# quad_decay_v1_0_2.net
KiCad netlist of a schematic drawn in EAGLE
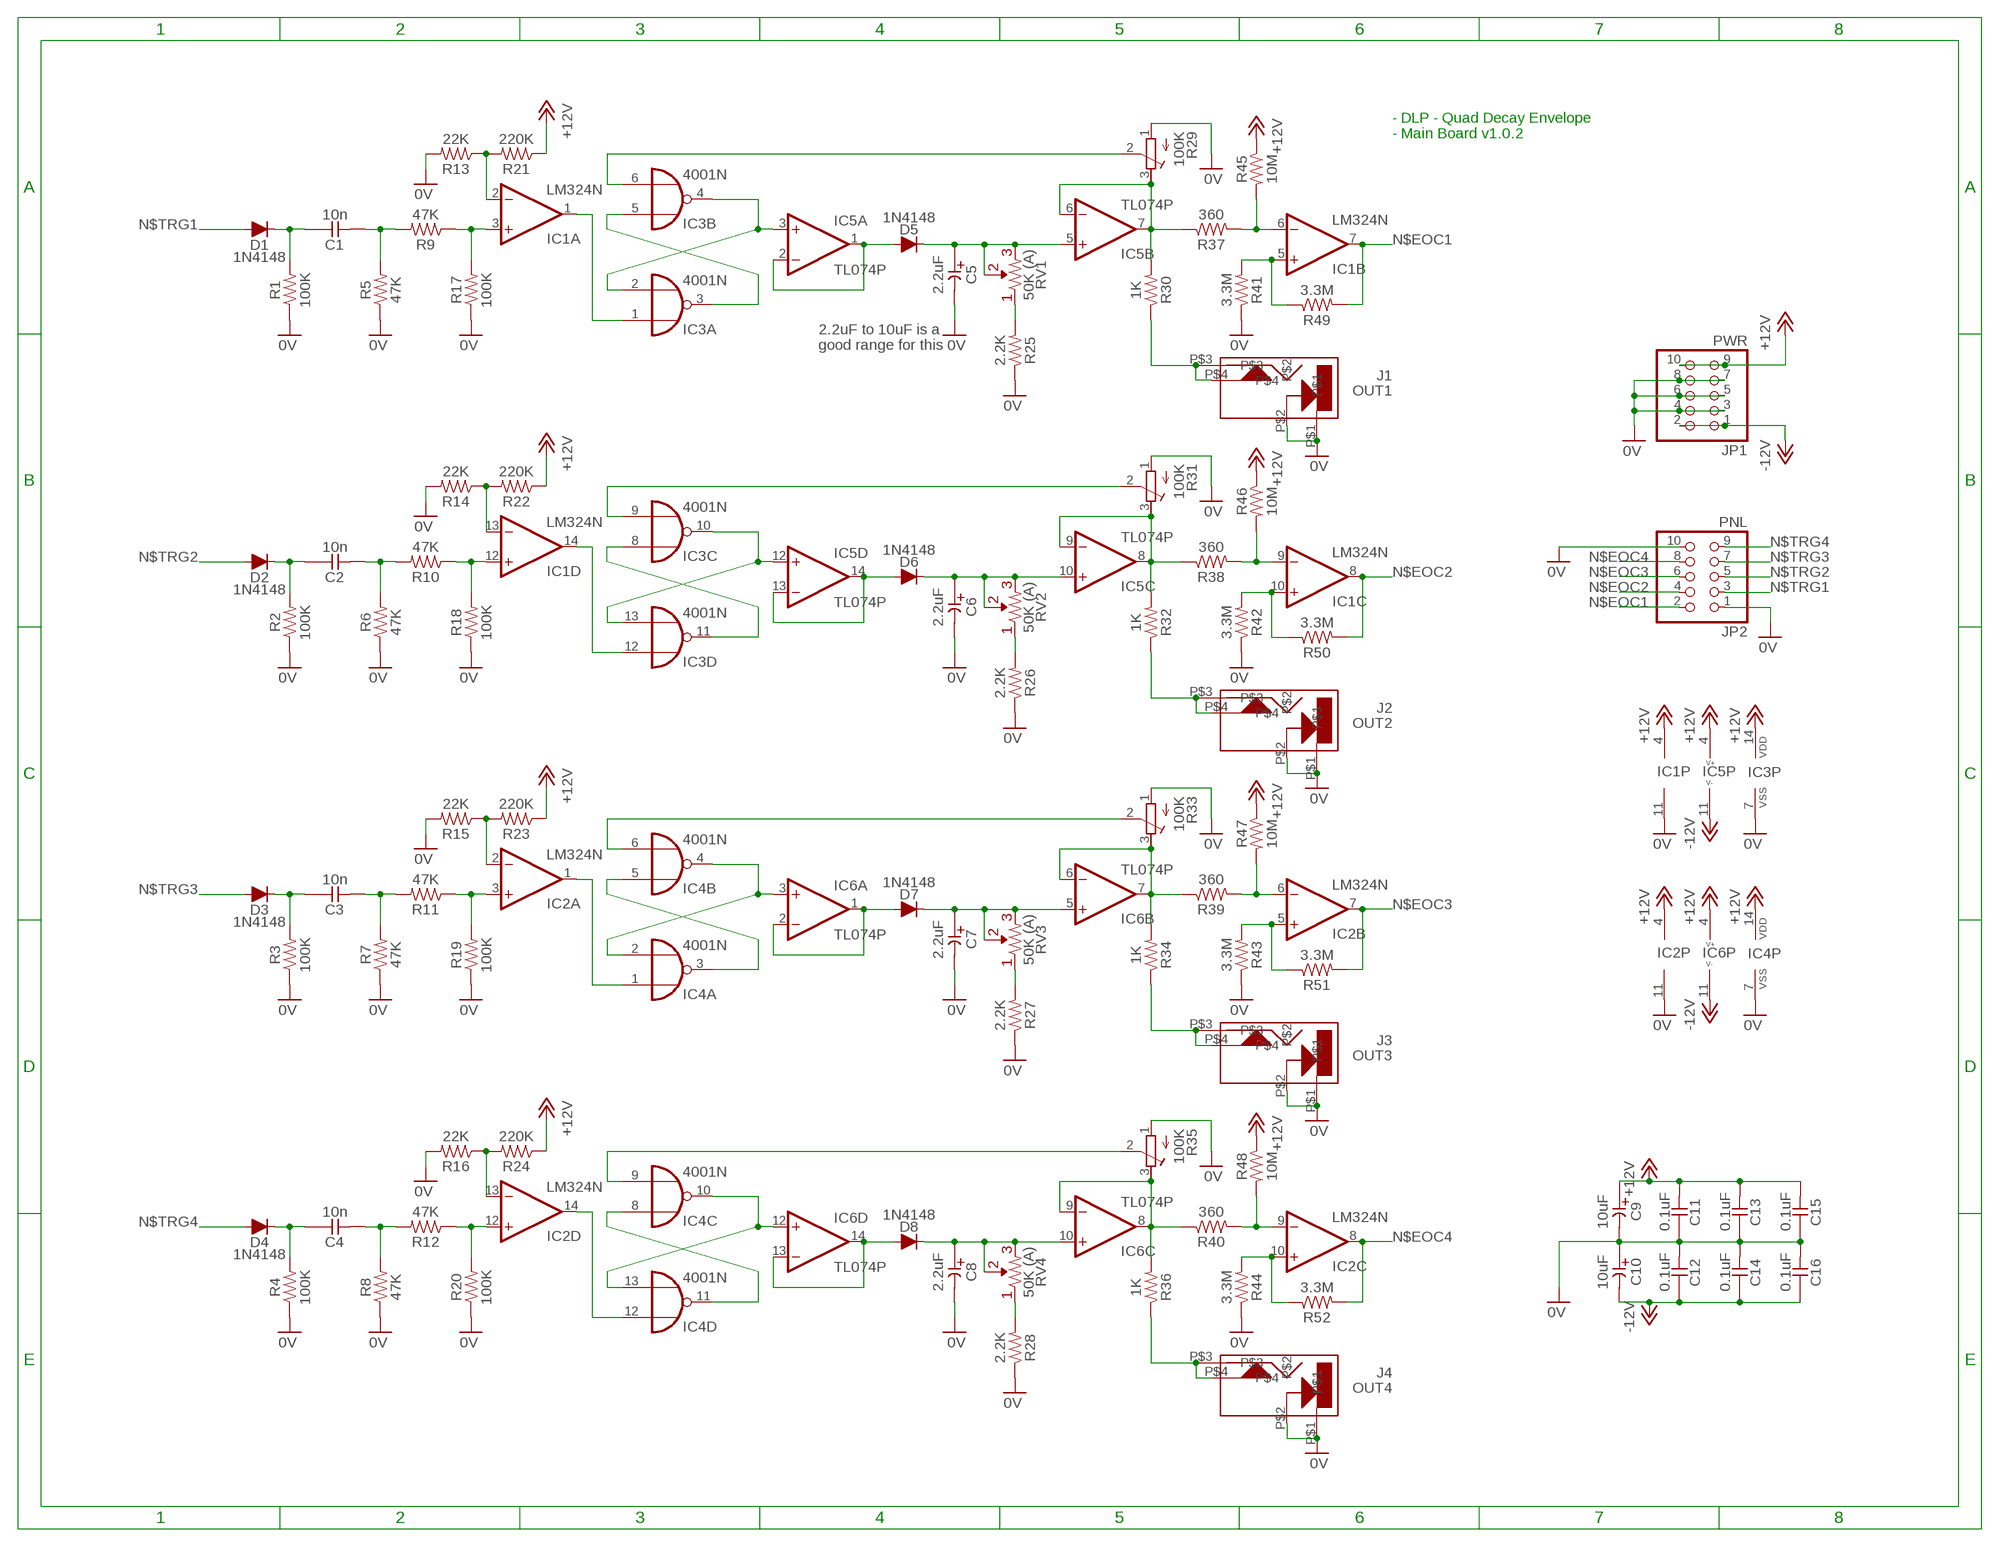
[diagram p0: schematic, sheet 1]

(export (version "E")
  (design (tool "Eeschema 10.0.6"))
  (components
    (comp (ref "C1")
      (value "10n")
      (footprint "eagle-import:C025-024X044")
      (libsource (lib "eagle-import") (part "CC-US025-024X044"))
    )
    (comp (ref "C2")
      (value "10n")
      (footprint "eagle-import:C025-024X044")
      (libsource (lib "eagle-import") (part "CC-US025-024X044"))
    )
    (comp (ref "C3")
      (value "10n")
      (footprint "eagle-import:C025-024X044")
      (libsource (lib "eagle-import") (part "CC-US025-024X044"))
    )
    (comp (ref "C4")
      (value "10n")
      (footprint "eagle-import:C025-024X044")
      (libsource (lib "eagle-import") (part "CC-US025-024X044"))
    )
    (comp (ref "C5")
      (value "2.2uF")
      (footprint "eagle-import:E2-5")
      (libsource (lib "eagle-import") (part "CE-USE2-5"))
    )
    (comp (ref "C6")
      (value "2.2uF")
      (footprint "eagle-import:E2-5")
      (libsource (lib "eagle-import") (part "CE-USE2-5"))
    )
    (comp (ref "C7")
      (value "2.2uF")
      (footprint "eagle-import:E2-5")
      (libsource (lib "eagle-import") (part "CE-USE2-5"))
    )
    (comp (ref "C8")
      (value "2.2uF")
      (footprint "eagle-import:E2-5")
      (libsource (lib "eagle-import") (part "CE-USE2-5"))
    )
    (comp (ref "C9")
      (value "10uF")
      (footprint "eagle-import:E2-5")
      (libsource (lib "eagle-import") (part "CE-USE2-5"))
    )
    (comp (ref "C10")
      (value "10uF")
      (footprint "eagle-import:E2-5")
      (libsource (lib "eagle-import") (part "CE-USE2-5"))
    )
    (comp (ref "C11")
      (value "0.1uF")
      (footprint "eagle-import:C025-024X044")
      (libsource (lib "eagle-import") (part "CC-US025-024X044"))
    )
    (comp (ref "C12")
      (value "0.1uF")
      (footprint "eagle-import:C025-024X044")
      (libsource (lib "eagle-import") (part "CC-US025-024X044"))
    )
    (comp (ref "C13")
      (value "0.1uF")
      (footprint "eagle-import:C025-024X044")
      (libsource (lib "eagle-import") (part "CC-US025-024X044"))
    )
    (comp (ref "C14")
      (value "0.1uF")
      (footprint "eagle-import:C025-024X044")
      (libsource (lib "eagle-import") (part "CC-US025-024X044"))
    )
    (comp (ref "C15")
      (value "0.1uF")
      (footprint "eagle-import:C025-024X044")
      (libsource (lib "eagle-import") (part "CC-US025-024X044"))
    )
    (comp (ref "C16")
      (value "0.1uF")
      (footprint "eagle-import:C025-024X044")
      (libsource (lib "eagle-import") (part "CC-US025-024X044"))
    )
    (comp (ref "D1")
      (value "1N4148")
      (footprint "eagle-import:DO34-5")
      (libsource (lib "eagle-import") (part "1N4148"))
    )
    (comp (ref "D2")
      (value "1N4148")
      (footprint "eagle-import:DO34-5")
      (libsource (lib "eagle-import") (part "1N4148"))
    )
    (comp (ref "D3")
      (value "1N4148")
      (footprint "eagle-import:DO34-5")
      (libsource (lib "eagle-import") (part "1N4148"))
    )
    (comp (ref "D4")
      (value "1N4148")
      (footprint "eagle-import:DO34-5")
      (libsource (lib "eagle-import") (part "1N4148"))
    )
    (comp (ref "D5")
      (value "1N4148")
      (footprint "eagle-import:DO34-5")
      (libsource (lib "eagle-import") (part "1N4148"))
    )
    (comp (ref "D6")
      (value "1N4148")
      (footprint "eagle-import:DO34-5")
      (libsource (lib "eagle-import") (part "1N4148"))
    )
    (comp (ref "D7")
      (value "1N4148")
      (footprint "eagle-import:DO34-5")
      (libsource (lib "eagle-import") (part "1N4148"))
    )
    (comp (ref "D8")
      (value "1N4148")
      (footprint "eagle-import:DO34-5")
      (libsource (lib "eagle-import") (part "1N4148"))
    )
    (comp (ref "IC1")
      (value "LM324N")
      (footprint "eagle-import:DIL14")
      (libsource (lib "eagle-import") (part "LM324N"))
    )
    (comp (ref "IC2")
      (value "LM324N")
      (footprint "eagle-import:DIL14")
      (libsource (lib "eagle-import") (part "LM324N"))
    )
    (comp (ref "IC3")
      (value "4001N")
      (footprint "eagle-import:DIL14")
      (libsource (lib "eagle-import") (part "4001N"))
    )
    (comp (ref "IC4")
      (value "4001N")
      (footprint "eagle-import:DIL14")
      (libsource (lib "eagle-import") (part "4001N"))
    )
    (comp (ref "IC5")
      (value "TL074P")
      (footprint "eagle-import:DIL14")
      (libsource (lib "eagle-import") (part "TL074P"))
    )
    (comp (ref "IC6")
      (value "TL074P")
      (footprint "eagle-import:DIL14")
      (libsource (lib "eagle-import") (part "TL074P"))
    )
    (comp (ref "J1")
      (value "OUT1")
      (footprint "eagle-import:CL1384")
      (libsource (lib "eagle-import") (part "CL1384"))
    )
    (comp (ref "J2")
      (value "OUT2")
      (footprint "eagle-import:CL1384")
      (libsource (lib "eagle-import") (part "CL1384"))
    )
    (comp (ref "J3")
      (value "OUT3")
      (footprint "eagle-import:CL1384")
      (libsource (lib "eagle-import") (part "CL1384"))
    )
    (comp (ref "J4")
      (value "OUT4")
      (footprint "eagle-import:CL1384")
      (libsource (lib "eagle-import") (part "CL1384"))
    )
    (comp (ref "JP1")
      (value "PWR")
      (footprint "eagle-import:2X05")
      (libsource (lib "eagle-import") (part "PINHD-2X5"))
    )
    (comp (ref "JP2")
      (value "PNL")
      (footprint "eagle-import:2X05")
      (libsource (lib "eagle-import") (part "PINHD-2X5"))
    )
    (comp (ref "R1")
      (value "100K")
      (footprint "eagle-import:0207_7")
      (libsource (lib "eagle-import") (part "R"))
    )
    (comp (ref "R2")
      (value "100K")
      (footprint "eagle-import:0207_7")
      (libsource (lib "eagle-import") (part "R"))
    )
    (comp (ref "R3")
      (value "100K")
      (footprint "eagle-import:0207_7")
      (libsource (lib "eagle-import") (part "R"))
    )
    (comp (ref "R4")
      (value "100K")
      (footprint "eagle-import:0207_7")
      (libsource (lib "eagle-import") (part "R"))
    )
    (comp (ref "R5")
      (value "47K")
      (footprint "eagle-import:0207_7")
      (libsource (lib "eagle-import") (part "R"))
    )
    (comp (ref "R6")
      (value "47K")
      (footprint "eagle-import:0207_7")
      (libsource (lib "eagle-import") (part "R"))
    )
    (comp (ref "R7")
      (value "47K")
      (footprint "eagle-import:0207_7")
      (libsource (lib "eagle-import") (part "R"))
    )
    (comp (ref "R8")
      (value "47K")
      (footprint "eagle-import:0207_7")
      (libsource (lib "eagle-import") (part "R"))
    )
    (comp (ref "R9")
      (value "47K")
      (footprint "eagle-import:0207_7")
      (libsource (lib "eagle-import") (part "R"))
    )
    (comp (ref "R10")
      (value "47K")
      (footprint "eagle-import:0207_7")
      (libsource (lib "eagle-import") (part "R"))
    )
    (comp (ref "R11")
      (value "47K")
      (footprint "eagle-import:0207_7")
      (libsource (lib "eagle-import") (part "R"))
    )
    (comp (ref "R12")
      (value "47K")
      (footprint "eagle-import:0207_7")
      (libsource (lib "eagle-import") (part "R"))
    )
    (comp (ref "R13")
      (value "22K")
      (footprint "eagle-import:0207_7")
      (libsource (lib "eagle-import") (part "R"))
    )
    (comp (ref "R14")
      (value "22K")
      (footprint "eagle-import:0207_7")
      (libsource (lib "eagle-import") (part "R"))
    )
    (comp (ref "R15")
      (value "22K")
      (footprint "eagle-import:0207_7")
      (libsource (lib "eagle-import") (part "R"))
    )
    (comp (ref "R16")
      (value "22K")
      (footprint "eagle-import:0207_7")
      (libsource (lib "eagle-import") (part "R"))
    )
    (comp (ref "R17")
      (value "100K")
      (footprint "eagle-import:0207_7")
      (libsource (lib "eagle-import") (part "R"))
    )
    (comp (ref "R18")
      (value "100K")
      (footprint "eagle-import:0207_7")
      (libsource (lib "eagle-import") (part "R"))
    )
    (comp (ref "R19")
      (value "100K")
      (footprint "eagle-import:0207_7")
      (libsource (lib "eagle-import") (part "R"))
    )
    (comp (ref "R20")
      (value "100K")
      (footprint "eagle-import:0207_7")
      (libsource (lib "eagle-import") (part "R"))
    )
    (comp (ref "R21")
      (value "220K")
      (footprint "eagle-import:0207_7")
      (libsource (lib "eagle-import") (part "R"))
    )
    (comp (ref "R22")
      (value "220K")
      (footprint "eagle-import:0207_7")
      (libsource (lib "eagle-import") (part "R"))
    )
    (comp (ref "R23")
      (value "220K")
      (footprint "eagle-import:0207_7")
      (libsource (lib "eagle-import") (part "R"))
    )
    (comp (ref "R24")
      (value "220K")
      (footprint "eagle-import:0207_7")
      (libsource (lib "eagle-import") (part "R"))
    )
    (comp (ref "R25")
      (value "2.2K")
      (footprint "eagle-import:0207_7")
      (libsource (lib "eagle-import") (part "R"))
    )
    (comp (ref "R26")
      (value "2.2K")
      (footprint "eagle-import:0207_7")
      (libsource (lib "eagle-import") (part "R"))
    )
    (comp (ref "R27")
      (value "2.2K")
      (footprint "eagle-import:0207_7")
      (libsource (lib "eagle-import") (part "R"))
    )
    (comp (ref "R28")
      (value "2.2K")
      (footprint "eagle-import:0207_7")
      (libsource (lib "eagle-import") (part "R"))
    )
    (comp (ref "R29")
      (value "100K")
      (footprint "eagle-import:RTRIM3339P")
      (libsource (lib "eagle-import") (part "R-TRIMM3339P"))
    )
    (comp (ref "R30")
      (value "1K")
      (footprint "eagle-import:0207_7")
      (libsource (lib "eagle-import") (part "R"))
    )
    (comp (ref "R31")
      (value "100K")
      (footprint "eagle-import:RTRIM3339P")
      (libsource (lib "eagle-import") (part "R-TRIMM3339P"))
    )
    (comp (ref "R32")
      (value "1K")
      (footprint "eagle-import:0207_7")
      (libsource (lib "eagle-import") (part "R"))
    )
    (comp (ref "R33")
      (value "100K")
      (footprint "eagle-import:RTRIM3339P")
      (libsource (lib "eagle-import") (part "R-TRIMM3339P"))
    )
    (comp (ref "R34")
      (value "1K")
      (footprint "eagle-import:0207_7")
      (libsource (lib "eagle-import") (part "R"))
    )
    (comp (ref "R35")
      (value "100K")
      (footprint "eagle-import:RTRIM3339P")
      (libsource (lib "eagle-import") (part "R-TRIMM3339P"))
    )
    (comp (ref "R36")
      (value "1K")
      (footprint "eagle-import:0207_7")
      (libsource (lib "eagle-import") (part "R"))
    )
    (comp (ref "R37")
      (value "360")
      (footprint "eagle-import:0207_7")
      (libsource (lib "eagle-import") (part "R"))
    )
    (comp (ref "R38")
      (value "360")
      (footprint "eagle-import:0207_7")
      (libsource (lib "eagle-import") (part "R"))
    )
    (comp (ref "R39")
      (value "360")
      (footprint "eagle-import:0207_7")
      (libsource (lib "eagle-import") (part "R"))
    )
    (comp (ref "R40")
      (value "360")
      (footprint "eagle-import:0207_7")
      (libsource (lib "eagle-import") (part "R"))
    )
    (comp (ref "R41")
      (value "3.3M")
      (footprint "eagle-import:0207_7")
      (libsource (lib "eagle-import") (part "R"))
    )
    (comp (ref "R42")
      (value "3.3M")
      (footprint "eagle-import:0207_7")
      (libsource (lib "eagle-import") (part "R"))
    )
    (comp (ref "R43")
      (value "3.3M")
      (footprint "eagle-import:0207_7")
      (libsource (lib "eagle-import") (part "R"))
    )
    (comp (ref "R44")
      (value "3.3M")
      (footprint "eagle-import:0207_7")
      (libsource (lib "eagle-import") (part "R"))
    )
    (comp (ref "R45")
      (value "10M")
      (footprint "eagle-import:0207_7")
      (libsource (lib "eagle-import") (part "R"))
    )
    (comp (ref "R46")
      (value "10M")
      (footprint "eagle-import:0207_7")
      (libsource (lib "eagle-import") (part "R"))
    )
    (comp (ref "R47")
      (value "10M")
      (footprint "eagle-import:0207_7")
      (libsource (lib "eagle-import") (part "R"))
    )
    (comp (ref "R48")
      (value "10M")
      (footprint "eagle-import:0207_7")
      (libsource (lib "eagle-import") (part "R"))
    )
    (comp (ref "R49")
      (value "3.3M")
      (footprint "eagle-import:0207_7")
      (libsource (lib "eagle-import") (part "R"))
    )
    (comp (ref "R50")
      (value "3.3M")
      (footprint "eagle-import:0207_7")
      (libsource (lib "eagle-import") (part "R"))
    )
    (comp (ref "R51")
      (value "3.3M")
      (footprint "eagle-import:0207_7")
      (libsource (lib "eagle-import") (part "R"))
    )
    (comp (ref "R52")
      (value "3.3M")
      (footprint "eagle-import:0207_7")
      (libsource (lib "eagle-import") (part "R"))
    )
    (comp (ref "RV1")
      (value "50K (A)")
      (footprint "eagle-import:R-VAR")
      (libsource (lib "eagle-import") (part "R-VAR"))
    )
    (comp (ref "RV2")
      (value "50K (A)")
      (footprint "eagle-import:R-VAR")
      (libsource (lib "eagle-import") (part "R-VAR"))
    )
    (comp (ref "RV3")
      (value "50K (A)")
      (footprint "eagle-import:R-VAR")
      (libsource (lib "eagle-import") (part "R-VAR"))
    )
    (comp (ref "RV4")
      (value "50K (A)")
      (footprint "eagle-import:R-VAR")
      (libsource (lib "eagle-import") (part "R-VAR"))
    )
  )
  (nets
    (net (code "1") (name "+12V") (class "Default")
      (node (ref "C11") (pin "2") (pinfunction "2_2") (pintype "passive"))
      (node (ref "C13") (pin "2") (pinfunction "2_2") (pintype "passive"))
      (node (ref "C15") (pin "2") (pinfunction "2_2") (pintype "passive"))
      (node (ref "C9") (pin "+") (pinfunction "+_+") (pintype "passive"))
      (node (ref "IC1") (pin "4") (pinfunction "V+_4") (pintype "power_in"))
      (node (ref "IC2") (pin "4") (pinfunction "V+_4") (pintype "power_in"))
      (node (ref "IC3") (pin "14") (pinfunction "VDD_14") (pintype "power_in"))
      (node (ref "IC4") (pin "14") (pinfunction "VDD_14") (pintype "power_in"))
      (node (ref "IC5") (pin "4") (pinfunction "V+_4") (pintype "power_in"))
      (node (ref "IC6") (pin "4") (pinfunction "V+_4") (pintype "power_in"))
      (node (ref "JP1") (pin "10") (pinfunction "10_10") (pintype "passive"))
      (node (ref "JP1") (pin "9") (pinfunction "9_9") (pintype "passive"))
      (node (ref "R21") (pin "1") (pinfunction "1_1") (pintype "passive"))
      (node (ref "R22") (pin "1") (pinfunction "1_1") (pintype "passive"))
      (node (ref "R23") (pin "1") (pinfunction "1_1") (pintype "passive"))
      (node (ref "R24") (pin "1") (pinfunction "1_1") (pintype "passive"))
      (node (ref "R45") (pin "1") (pinfunction "1_1") (pintype "passive"))
      (node (ref "R46") (pin "1") (pinfunction "1_1") (pintype "passive"))
      (node (ref "R47") (pin "1") (pinfunction "1_1") (pintype "passive"))
      (node (ref "R48") (pin "1") (pinfunction "1_1") (pintype "passive"))
    )
    (net (code "2") (name "-12V") (class "Default")
      (node (ref "C10") (pin "-") (pinfunction "-_-") (pintype "passive"))
      (node (ref "C12") (pin "1") (pinfunction "1_1") (pintype "passive"))
      (node (ref "C14") (pin "1") (pinfunction "1_1") (pintype "passive"))
      (node (ref "C16") (pin "1") (pinfunction "1_1") (pintype "passive"))
      (node (ref "IC5") (pin "11") (pinfunction "V-_11") (pintype "power_in"))
      (node (ref "IC6") (pin "11") (pinfunction "V-_11") (pintype "power_in"))
      (node (ref "JP1") (pin "1") (pinfunction "1_1") (pintype "passive"))
      (node (ref "JP1") (pin "2") (pinfunction "2_2") (pintype "passive"))
    )
    (net (code "3") (name "/N$EOC1") (class "Default")
      (node (ref "IC1") (pin "7") (pinfunction "OUT_7") (pintype "output"))
      (node (ref "JP2") (pin "2") (pinfunction "2_2") (pintype "passive"))
      (node (ref "R49") (pin "2") (pinfunction "2_2") (pintype "passive"))
    )
    (net (code "4") (name "/N$EOC2") (class "Default")
      (node (ref "IC1") (pin "8") (pinfunction "OUT_8") (pintype "output"))
      (node (ref "JP2") (pin "4") (pinfunction "4_4") (pintype "passive"))
      (node (ref "R50") (pin "2") (pinfunction "2_2") (pintype "passive"))
    )
    (net (code "5") (name "/N$EOC3") (class "Default")
      (node (ref "IC2") (pin "7") (pinfunction "OUT_7") (pintype "output"))
      (node (ref "JP2") (pin "6") (pinfunction "6_6") (pintype "passive"))
      (node (ref "R51") (pin "2") (pinfunction "2_2") (pintype "passive"))
    )
    (net (code "6") (name "/N$EOC4") (class "Default")
      (node (ref "IC2") (pin "8") (pinfunction "OUT_8") (pintype "output"))
      (node (ref "JP2") (pin "8") (pinfunction "8_8") (pintype "passive"))
      (node (ref "R52") (pin "2") (pinfunction "2_2") (pintype "passive"))
    )
    (net (code "7") (name "/N$TRG1") (class "Default")
      (node (ref "D1") (pin "A") (pinfunction "A_A") (pintype "passive"))
      (node (ref "JP2") (pin "3") (pinfunction "3_3") (pintype "passive"))
    )
    (net (code "8") (name "/N$TRG2") (class "Default")
      (node (ref "D2") (pin "A") (pinfunction "A_A") (pintype "passive"))
      (node (ref "JP2") (pin "5") (pinfunction "5_5") (pintype "passive"))
    )
    (net (code "9") (name "/N$TRG3") (class "Default")
      (node (ref "D3") (pin "A") (pinfunction "A_A") (pintype "passive"))
      (node (ref "JP2") (pin "7") (pinfunction "7_7") (pintype "passive"))
    )
    (net (code "10") (name "/N$TRG4") (class "Default")
      (node (ref "D4") (pin "A") (pinfunction "A_A") (pintype "passive"))
      (node (ref "JP2") (pin "9") (pinfunction "9_9") (pintype "passive"))
    )
    (net (code "11") (name "0V") (class "Default")
      (node (ref "C10") (pin "+") (pinfunction "+_+") (pintype "passive"))
      (node (ref "C11") (pin "1") (pinfunction "1_1") (pintype "passive"))
      (node (ref "C12") (pin "2") (pinfunction "2_2") (pintype "passive"))
      (node (ref "C13") (pin "1") (pinfunction "1_1") (pintype "passive"))
      (node (ref "C14") (pin "2") (pinfunction "2_2") (pintype "passive"))
      (node (ref "C15") (pin "1") (pinfunction "1_1") (pintype "passive"))
      (node (ref "C16") (pin "2") (pinfunction "2_2") (pintype "passive"))
      (node (ref "C5") (pin "-") (pinfunction "-_-") (pintype "passive"))
      (node (ref "C6") (pin "-") (pinfunction "-_-") (pintype "passive"))
      (node (ref "C7") (pin "-") (pinfunction "-_-") (pintype "passive"))
      (node (ref "C8") (pin "-") (pinfunction "-_-") (pintype "passive"))
      (node (ref "C9") (pin "-") (pinfunction "-_-") (pintype "passive"))
      (node (ref "IC1") (pin "11") (pinfunction "V-_11") (pintype "power_in"))
      (node (ref "IC2") (pin "11") (pinfunction "V-_11") (pintype "power_in"))
      (node (ref "IC3") (pin "7") (pinfunction "VSS_7") (pintype "power_in"))
      (node (ref "IC4") (pin "7") (pinfunction "VSS_7") (pintype "power_in"))
      (node (ref "J1") (pin "P$1") (pinfunction "P$1_P$1") (pintype "bidirectional"))
      (node (ref "J1") (pin "P$2") (pinfunction "P$2_P$2") (pintype "bidirectional"))
      (node (ref "J2") (pin "P$1") (pinfunction "P$1_P$1") (pintype "bidirectional"))
      (node (ref "J2") (pin "P$2") (pinfunction "P$2_P$2") (pintype "bidirectional"))
      (node (ref "J3") (pin "P$1") (pinfunction "P$1_P$1") (pintype "bidirectional"))
      (node (ref "J3") (pin "P$2") (pinfunction "P$2_P$2") (pintype "bidirectional"))
      (node (ref "J4") (pin "P$1") (pinfunction "P$1_P$1") (pintype "bidirectional"))
      (node (ref "J4") (pin "P$2") (pinfunction "P$2_P$2") (pintype "bidirectional"))
      (node (ref "JP1") (pin "3") (pinfunction "3_3") (pintype "passive"))
      (node (ref "JP1") (pin "4") (pinfunction "4_4") (pintype "passive"))
      (node (ref "JP1") (pin "5") (pinfunction "5_5") (pintype "passive"))
      (node (ref "JP1") (pin "6") (pinfunction "6_6") (pintype "passive"))
      (node (ref "JP1") (pin "7") (pinfunction "7_7") (pintype "passive"))
      (node (ref "JP1") (pin "8") (pinfunction "8_8") (pintype "passive"))
      (node (ref "JP2") (pin "1") (pinfunction "1_1") (pintype "passive"))
      (node (ref "JP2") (pin "10") (pinfunction "10_10") (pintype "passive"))
      (node (ref "R1") (pin "1") (pinfunction "1_1") (pintype "passive"))
      (node (ref "R13") (pin "2") (pinfunction "2_2") (pintype "passive"))
      (node (ref "R14") (pin "2") (pinfunction "2_2") (pintype "passive"))
      (node (ref "R15") (pin "2") (pinfunction "2_2") (pintype "passive"))
      (node (ref "R16") (pin "2") (pinfunction "2_2") (pintype "passive"))
      (node (ref "R17") (pin "1") (pinfunction "1_1") (pintype "passive"))
      (node (ref "R18") (pin "1") (pinfunction "1_1") (pintype "passive"))
      (node (ref "R19") (pin "1") (pinfunction "1_1") (pintype "passive"))
      (node (ref "R2") (pin "1") (pinfunction "1_1") (pintype "passive"))
      (node (ref "R20") (pin "1") (pinfunction "1_1") (pintype "passive"))
      (node (ref "R25") (pin "1") (pinfunction "1_1") (pintype "passive"))
      (node (ref "R26") (pin "1") (pinfunction "1_1") (pintype "passive"))
      (node (ref "R27") (pin "1") (pinfunction "1_1") (pintype "passive"))
      (node (ref "R28") (pin "1") (pinfunction "1_1") (pintype "passive"))
      (node (ref "R29") (pin "1") (pinfunction "A_1") (pintype "passive"))
      (node (ref "R3") (pin "1") (pinfunction "1_1") (pintype "passive"))
      (node (ref "R31") (pin "1") (pinfunction "A_1") (pintype "passive"))
      (node (ref "R33") (pin "1") (pinfunction "A_1") (pintype "passive"))
      (node (ref "R35") (pin "1") (pinfunction "A_1") (pintype "passive"))
      (node (ref "R4") (pin "1") (pinfunction "1_1") (pintype "passive"))
      (node (ref "R41") (pin "1") (pinfunction "1_1") (pintype "passive"))
      (node (ref "R42") (pin "1") (pinfunction "1_1") (pintype "passive"))
      (node (ref "R43") (pin "1") (pinfunction "1_1") (pintype "passive"))
      (node (ref "R44") (pin "1") (pinfunction "1_1") (pintype "passive"))
      (node (ref "R5") (pin "1") (pinfunction "1_1") (pintype "passive"))
      (node (ref "R6") (pin "1") (pinfunction "1_1") (pintype "passive"))
      (node (ref "R7") (pin "1") (pinfunction "1_1") (pintype "passive"))
      (node (ref "R8") (pin "1") (pinfunction "1_1") (pintype "passive"))
    )
    (net (code "12") (name "Net-(C1-Pad1)") (class "Default")
      (node (ref "C1") (pin "1") (pinfunction "1_1") (pintype "passive"))
      (node (ref "D1") (pin "C") (pinfunction "C_C") (pintype "passive"))
      (node (ref "R1") (pin "2") (pinfunction "2_2") (pintype "passive"))
    )
    (net (code "13") (name "Net-(C1-Pad2)") (class "Default")
      (node (ref "C1") (pin "2") (pinfunction "2_2") (pintype "passive"))
      (node (ref "R5") (pin "2") (pinfunction "2_2") (pintype "passive"))
      (node (ref "R9") (pin "2") (pinfunction "2_2") (pintype "passive"))
    )
    (net (code "14") (name "Net-(C2-Pad1)") (class "Default")
      (node (ref "C2") (pin "1") (pinfunction "1_1") (pintype "passive"))
      (node (ref "D2") (pin "C") (pinfunction "C_C") (pintype "passive"))
      (node (ref "R2") (pin "2") (pinfunction "2_2") (pintype "passive"))
    )
    (net (code "15") (name "Net-(C2-Pad2)") (class "Default")
      (node (ref "C2") (pin "2") (pinfunction "2_2") (pintype "passive"))
      (node (ref "R10") (pin "2") (pinfunction "2_2") (pintype "passive"))
      (node (ref "R6") (pin "2") (pinfunction "2_2") (pintype "passive"))
    )
    (net (code "16") (name "Net-(C3-Pad1)") (class "Default")
      (node (ref "C3") (pin "1") (pinfunction "1_1") (pintype "passive"))
      (node (ref "D3") (pin "C") (pinfunction "C_C") (pintype "passive"))
      (node (ref "R3") (pin "2") (pinfunction "2_2") (pintype "passive"))
    )
    (net (code "17") (name "Net-(C3-Pad2)") (class "Default")
      (node (ref "C3") (pin "2") (pinfunction "2_2") (pintype "passive"))
      (node (ref "R11") (pin "2") (pinfunction "2_2") (pintype "passive"))
      (node (ref "R7") (pin "2") (pinfunction "2_2") (pintype "passive"))
    )
    (net (code "18") (name "Net-(C4-Pad1)") (class "Default")
      (node (ref "C4") (pin "1") (pinfunction "1_1") (pintype "passive"))
      (node (ref "D4") (pin "C") (pinfunction "C_C") (pintype "passive"))
      (node (ref "R4") (pin "2") (pinfunction "2_2") (pintype "passive"))
    )
    (net (code "19") (name "Net-(C4-Pad2)") (class "Default")
      (node (ref "C4") (pin "2") (pinfunction "2_2") (pintype "passive"))
      (node (ref "R12") (pin "2") (pinfunction "2_2") (pintype "passive"))
      (node (ref "R8") (pin "2") (pinfunction "2_2") (pintype "passive"))
    )
    (net (code "20") (name "Net-(IC1A-+IN)") (class "Default")
      (node (ref "IC1") (pin "3") (pinfunction "+IN_3") (pintype "input"))
      (node (ref "R17") (pin "2") (pinfunction "2_2") (pintype "passive"))
      (node (ref "R9") (pin "1") (pinfunction "1_1") (pintype "passive"))
    )
    (net (code "21") (name "Net-(IC1A--IN)") (class "Default")
      (node (ref "IC1") (pin "2") (pinfunction "-IN_2") (pintype "input"))
      (node (ref "R13") (pin "1") (pinfunction "1_1") (pintype "passive"))
      (node (ref "R21") (pin "2") (pinfunction "2_2") (pintype "passive"))
    )
    (net (code "22") (name "Net-(IC1A-OUT)") (class "Default")
      (node (ref "IC1") (pin "1") (pinfunction "OUT_1") (pintype "output"))
      (node (ref "IC3") (pin "1") (pinfunction "I0_1") (pintype "input"))
    )
    (net (code "23") (name "Net-(IC1B-+IN)") (class "Default")
      (node (ref "IC1") (pin "5") (pinfunction "+IN_5") (pintype "input"))
      (node (ref "R41") (pin "2") (pinfunction "2_2") (pintype "passive"))
      (node (ref "R49") (pin "1") (pinfunction "1_1") (pintype "passive"))
    )
    (net (code "24") (name "Net-(IC1B--IN)") (class "Default")
      (node (ref "IC1") (pin "6") (pinfunction "-IN_6") (pintype "input"))
      (node (ref "R37") (pin "2") (pinfunction "2_2") (pintype "passive"))
      (node (ref "R45") (pin "2") (pinfunction "2_2") (pintype "passive"))
    )
    (net (code "25") (name "Net-(IC1C-+IN)") (class "Default")
      (node (ref "IC1") (pin "10") (pinfunction "+IN_10") (pintype "input"))
      (node (ref "R42") (pin "2") (pinfunction "2_2") (pintype "passive"))
      (node (ref "R50") (pin "1") (pinfunction "1_1") (pintype "passive"))
    )
    (net (code "26") (name "Net-(IC1C--IN)") (class "Default")
      (node (ref "IC1") (pin "9") (pinfunction "-IN_9") (pintype "input"))
      (node (ref "R38") (pin "2") (pinfunction "2_2") (pintype "passive"))
      (node (ref "R46") (pin "2") (pinfunction "2_2") (pintype "passive"))
    )
    (net (code "27") (name "Net-(IC1D-+IN)") (class "Default")
      (node (ref "IC1") (pin "12") (pinfunction "+IN_12") (pintype "input"))
      (node (ref "R10") (pin "1") (pinfunction "1_1") (pintype "passive"))
      (node (ref "R18") (pin "2") (pinfunction "2_2") (pintype "passive"))
    )
    (net (code "28") (name "Net-(IC1D--IN)") (class "Default")
      (node (ref "IC1") (pin "13") (pinfunction "-IN_13") (pintype "input"))
      (node (ref "R14") (pin "1") (pinfunction "1_1") (pintype "passive"))
      (node (ref "R22") (pin "2") (pinfunction "2_2") (pintype "passive"))
    )
    (net (code "29") (name "Net-(IC1D-OUT)") (class "Default")
      (node (ref "IC1") (pin "14") (pinfunction "OUT_14") (pintype "output"))
      (node (ref "IC3") (pin "12") (pinfunction "I0_12") (pintype "input"))
    )
    (net (code "30") (name "Net-(IC2A-+IN)") (class "Default")
      (node (ref "IC2") (pin "3") (pinfunction "+IN_3") (pintype "input"))
      (node (ref "R11") (pin "1") (pinfunction "1_1") (pintype "passive"))
      (node (ref "R19") (pin "2") (pinfunction "2_2") (pintype "passive"))
    )
    (net (code "31") (name "Net-(IC2A--IN)") (class "Default")
      (node (ref "IC2") (pin "2") (pinfunction "-IN_2") (pintype "input"))
      (node (ref "R15") (pin "1") (pinfunction "1_1") (pintype "passive"))
      (node (ref "R23") (pin "2") (pinfunction "2_2") (pintype "passive"))
    )
    (net (code "32") (name "Net-(IC2A-OUT)") (class "Default")
      (node (ref "IC2") (pin "1") (pinfunction "OUT_1") (pintype "output"))
      (node (ref "IC4") (pin "1") (pinfunction "I0_1") (pintype "input"))
    )
    (net (code "33") (name "Net-(IC2B-+IN)") (class "Default")
      (node (ref "IC2") (pin "5") (pinfunction "+IN_5") (pintype "input"))
      (node (ref "R43") (pin "2") (pinfunction "2_2") (pintype "passive"))
      (node (ref "R51") (pin "1") (pinfunction "1_1") (pintype "passive"))
    )
    (net (code "34") (name "Net-(IC2B--IN)") (class "Default")
      (node (ref "IC2") (pin "6") (pinfunction "-IN_6") (pintype "input"))
      (node (ref "R39") (pin "2") (pinfunction "2_2") (pintype "passive"))
      (node (ref "R47") (pin "2") (pinfunction "2_2") (pintype "passive"))
    )
    (net (code "35") (name "Net-(IC2C-+IN)") (class "Default")
      (node (ref "IC2") (pin "10") (pinfunction "+IN_10") (pintype "input"))
      (node (ref "R44") (pin "2") (pinfunction "2_2") (pintype "passive"))
      (node (ref "R52") (pin "1") (pinfunction "1_1") (pintype "passive"))
    )
    (net (code "36") (name "Net-(IC2C--IN)") (class "Default")
      (node (ref "IC2") (pin "9") (pinfunction "-IN_9") (pintype "input"))
      (node (ref "R40") (pin "2") (pinfunction "2_2") (pintype "passive"))
      (node (ref "R48") (pin "2") (pinfunction "2_2") (pintype "passive"))
    )
    (net (code "37") (name "Net-(IC2D-+IN)") (class "Default")
      (node (ref "IC2") (pin "12") (pinfunction "+IN_12") (pintype "input"))
      (node (ref "R12") (pin "1") (pinfunction "1_1") (pintype "passive"))
      (node (ref "R20") (pin "2") (pinfunction "2_2") (pintype "passive"))
    )
    (net (code "38") (name "Net-(IC2D--IN)") (class "Default")
      (node (ref "IC2") (pin "13") (pinfunction "-IN_13") (pintype "input"))
      (node (ref "R16") (pin "1") (pinfunction "1_1") (pintype "passive"))
      (node (ref "R24") (pin "2") (pinfunction "2_2") (pintype "passive"))
    )
    (net (code "39") (name "Net-(IC2D-OUT)") (class "Default")
      (node (ref "IC2") (pin "14") (pinfunction "OUT_14") (pintype "output"))
      (node (ref "IC4") (pin "12") (pinfunction "I0_12") (pintype "input"))
    )
    (net (code "40") (name "Net-(IC3A-I1)") (class "Default")
      (node (ref "IC3") (pin "2") (pinfunction "I1_2") (pintype "input"))
      (node (ref "IC3") (pin "4") (pinfunction "O_4") (pintype "output"))
      (node (ref "IC5") (pin "3") (pinfunction "+IN_3") (pintype "input"))
    )
    (net (code "41") (name "Net-(IC3A-O)") (class "Default")
      (node (ref "IC3") (pin "3") (pinfunction "O_3") (pintype "output"))
      (node (ref "IC3") (pin "5") (pinfunction "I0_5") (pintype "input"))
    )
    (net (code "42") (name "Net-(IC3B-I1)") (class "Default")
      (node (ref "IC3") (pin "6") (pinfunction "I1_6") (pintype "input"))
      (node (ref "R29") (pin "2") (pinfunction "S_2") (pintype "passive"))
    )
    (net (code "43") (name "Net-(IC3C-I0)") (class "Default")
      (node (ref "IC3") (pin "11") (pinfunction "O_11") (pintype "output"))
      (node (ref "IC3") (pin "8") (pinfunction "I0_8") (pintype "input"))
    )
    (net (code "44") (name "Net-(IC3C-I1)") (class "Default")
      (node (ref "IC3") (pin "9") (pinfunction "I1_9") (pintype "input"))
      (node (ref "R31") (pin "2") (pinfunction "S_2") (pintype "passive"))
    )
    (net (code "45") (name "Net-(IC3C-O)") (class "Default")
      (node (ref "IC3") (pin "10") (pinfunction "O_10") (pintype "output"))
      (node (ref "IC3") (pin "13") (pinfunction "I1_13") (pintype "input"))
      (node (ref "IC5") (pin "12") (pinfunction "+IN_12") (pintype "input"))
    )
    (net (code "46") (name "Net-(IC4A-I1)") (class "Default")
      (node (ref "IC4") (pin "2") (pinfunction "I1_2") (pintype "input"))
      (node (ref "IC4") (pin "4") (pinfunction "O_4") (pintype "output"))
      (node (ref "IC6") (pin "3") (pinfunction "+IN_3") (pintype "input"))
    )
    (net (code "47") (name "Net-(IC4A-O)") (class "Default")
      (node (ref "IC4") (pin "3") (pinfunction "O_3") (pintype "output"))
      (node (ref "IC4") (pin "5") (pinfunction "I0_5") (pintype "input"))
    )
    (net (code "48") (name "Net-(IC4B-I1)") (class "Default")
      (node (ref "IC4") (pin "6") (pinfunction "I1_6") (pintype "input"))
      (node (ref "R33") (pin "2") (pinfunction "S_2") (pintype "passive"))
    )
    (net (code "49") (name "Net-(IC4C-I0)") (class "Default")
      (node (ref "IC4") (pin "11") (pinfunction "O_11") (pintype "output"))
      (node (ref "IC4") (pin "8") (pinfunction "I0_8") (pintype "input"))
    )
    (net (code "50") (name "Net-(IC4C-I1)") (class "Default")
      (node (ref "IC4") (pin "9") (pinfunction "I1_9") (pintype "input"))
      (node (ref "R35") (pin "2") (pinfunction "S_2") (pintype "passive"))
    )
    (net (code "51") (name "Net-(IC4C-O)") (class "Default")
      (node (ref "IC4") (pin "10") (pinfunction "O_10") (pintype "output"))
      (node (ref "IC4") (pin "13") (pinfunction "I1_13") (pintype "input"))
      (node (ref "IC6") (pin "12") (pinfunction "+IN_12") (pintype "input"))
    )
    (net (code "52") (name "Net-(IC5A--IN)") (class "Default")
      (node (ref "D5") (pin "A") (pinfunction "A_A") (pintype "passive"))
      (node (ref "IC5") (pin "1") (pinfunction "OUT_1") (pintype "output"))
      (node (ref "IC5") (pin "2") (pinfunction "-IN_2") (pintype "input"))
    )
    (net (code "53") (name "Net-(IC5B-+IN)") (class "Default")
      (node (ref "C5") (pin "+") (pinfunction "+_+") (pintype "passive"))
      (node (ref "D5") (pin "C") (pinfunction "C_C") (pintype "passive"))
      (node (ref "IC5") (pin "5") (pinfunction "+IN_5") (pintype "input"))
      (node (ref "RV1") (pin "R2") (pinfunction "2_R2") (pintype "passive"))
      (node (ref "RV1") (pin "VAR") (pinfunction "P$1_VAR") (pintype "passive"))
    )
    (net (code "54") (name "Net-(IC5B--IN)") (class "Default")
      (node (ref "IC5") (pin "6") (pinfunction "-IN_6") (pintype "input"))
      (node (ref "IC5") (pin "7") (pinfunction "OUT_7") (pintype "output"))
      (node (ref "R29") (pin "3") (pinfunction "E_3") (pintype "passive"))
      (node (ref "R30") (pin "2") (pinfunction "2_2") (pintype "passive"))
      (node (ref "R37") (pin "1") (pinfunction "1_1") (pintype "passive"))
    )
    (net (code "55") (name "Net-(IC5C-+IN)") (class "Default")
      (node (ref "C6") (pin "+") (pinfunction "+_+") (pintype "passive"))
      (node (ref "D6") (pin "C") (pinfunction "C_C") (pintype "passive"))
      (node (ref "IC5") (pin "10") (pinfunction "+IN_10") (pintype "input"))
      (node (ref "RV2") (pin "R2") (pinfunction "2_R2") (pintype "passive"))
      (node (ref "RV2") (pin "VAR") (pinfunction "P$1_VAR") (pintype "passive"))
    )
    (net (code "56") (name "Net-(IC5C--IN)") (class "Default")
      (node (ref "IC5") (pin "8") (pinfunction "OUT_8") (pintype "output"))
      (node (ref "IC5") (pin "9") (pinfunction "-IN_9") (pintype "input"))
      (node (ref "R31") (pin "3") (pinfunction "E_3") (pintype "passive"))
      (node (ref "R32") (pin "2") (pinfunction "2_2") (pintype "passive"))
      (node (ref "R38") (pin "1") (pinfunction "1_1") (pintype "passive"))
    )
    (net (code "57") (name "Net-(IC5D--IN)") (class "Default")
      (node (ref "D6") (pin "A") (pinfunction "A_A") (pintype "passive"))
      (node (ref "IC5") (pin "13") (pinfunction "-IN_13") (pintype "input"))
      (node (ref "IC5") (pin "14") (pinfunction "OUT_14") (pintype "output"))
    )
    (net (code "58") (name "Net-(IC6A--IN)") (class "Default")
      (node (ref "D7") (pin "A") (pinfunction "A_A") (pintype "passive"))
      (node (ref "IC6") (pin "1") (pinfunction "OUT_1") (pintype "output"))
      (node (ref "IC6") (pin "2") (pinfunction "-IN_2") (pintype "input"))
    )
    (net (code "59") (name "Net-(IC6B-+IN)") (class "Default")
      (node (ref "C7") (pin "+") (pinfunction "+_+") (pintype "passive"))
      (node (ref "D7") (pin "C") (pinfunction "C_C") (pintype "passive"))
      (node (ref "IC6") (pin "5") (pinfunction "+IN_5") (pintype "input"))
      (node (ref "RV3") (pin "R2") (pinfunction "2_R2") (pintype "passive"))
      (node (ref "RV3") (pin "VAR") (pinfunction "P$1_VAR") (pintype "passive"))
    )
    (net (code "60") (name "Net-(IC6B--IN)") (class "Default")
      (node (ref "IC6") (pin "6") (pinfunction "-IN_6") (pintype "input"))
      (node (ref "IC6") (pin "7") (pinfunction "OUT_7") (pintype "output"))
      (node (ref "R33") (pin "3") (pinfunction "E_3") (pintype "passive"))
      (node (ref "R34") (pin "2") (pinfunction "2_2") (pintype "passive"))
      (node (ref "R39") (pin "1") (pinfunction "1_1") (pintype "passive"))
    )
    (net (code "61") (name "Net-(IC6C-+IN)") (class "Default")
      (node (ref "C8") (pin "+") (pinfunction "+_+") (pintype "passive"))
      (node (ref "D8") (pin "C") (pinfunction "C_C") (pintype "passive"))
      (node (ref "IC6") (pin "10") (pinfunction "+IN_10") (pintype "input"))
      (node (ref "RV4") (pin "R2") (pinfunction "2_R2") (pintype "passive"))
      (node (ref "RV4") (pin "VAR") (pinfunction "P$1_VAR") (pintype "passive"))
    )
    (net (code "62") (name "Net-(IC6C--IN)") (class "Default")
      (node (ref "IC6") (pin "8") (pinfunction "OUT_8") (pintype "output"))
      (node (ref "IC6") (pin "9") (pinfunction "-IN_9") (pintype "input"))
      (node (ref "R35") (pin "3") (pinfunction "E_3") (pintype "passive"))
      (node (ref "R36") (pin "2") (pinfunction "2_2") (pintype "passive"))
      (node (ref "R40") (pin "1") (pinfunction "1_1") (pintype "passive"))
    )
    (net (code "63") (name "Net-(IC6D--IN)") (class "Default")
      (node (ref "D8") (pin "A") (pinfunction "A_A") (pintype "passive"))
      (node (ref "IC6") (pin "13") (pinfunction "-IN_13") (pintype "input"))
      (node (ref "IC6") (pin "14") (pinfunction "OUT_14") (pintype "output"))
    )
    (net (code "64") (name "Net-(J1-PadP$3)") (class "Default")
      (node (ref "J1") (pin "P$3") (pinfunction "P$3_P$3") (pintype "bidirectional"))
      (node (ref "J1") (pin "P$4") (pinfunction "P$4_P$4") (pintype "bidirectional"))
      (node (ref "R30") (pin "1") (pinfunction "1_1") (pintype "passive"))
    )
    (net (code "65") (name "Net-(J2-PadP$3)") (class "Default")
      (node (ref "J2") (pin "P$3") (pinfunction "P$3_P$3") (pintype "bidirectional"))
      (node (ref "J2") (pin "P$4") (pinfunction "P$4_P$4") (pintype "bidirectional"))
      (node (ref "R32") (pin "1") (pinfunction "1_1") (pintype "passive"))
    )
    (net (code "66") (name "Net-(J3-PadP$3)") (class "Default")
      (node (ref "J3") (pin "P$3") (pinfunction "P$3_P$3") (pintype "bidirectional"))
      (node (ref "J3") (pin "P$4") (pinfunction "P$4_P$4") (pintype "bidirectional"))
      (node (ref "R34") (pin "1") (pinfunction "1_1") (pintype "passive"))
    )
    (net (code "67") (name "Net-(J4-PadP$3)") (class "Default")
      (node (ref "J4") (pin "P$3") (pinfunction "P$3_P$3") (pintype "bidirectional"))
      (node (ref "J4") (pin "P$4") (pinfunction "P$4_P$4") (pintype "bidirectional"))
      (node (ref "R36") (pin "1") (pinfunction "1_1") (pintype "passive"))
    )
    (net (code "68") (name "Net-(RV1-1)") (class "Default")
      (node (ref "R25") (pin "2") (pinfunction "2_2") (pintype "passive"))
      (node (ref "RV1") (pin "R1") (pinfunction "1_R1") (pintype "passive"))
    )
    (net (code "69") (name "Net-(RV2-1)") (class "Default")
      (node (ref "R26") (pin "2") (pinfunction "2_2") (pintype "passive"))
      (node (ref "RV2") (pin "R1") (pinfunction "1_R1") (pintype "passive"))
    )
    (net (code "70") (name "Net-(RV3-1)") (class "Default")
      (node (ref "R27") (pin "2") (pinfunction "2_2") (pintype "passive"))
      (node (ref "RV3") (pin "R1") (pinfunction "1_R1") (pintype "passive"))
    )
    (net (code "71") (name "Net-(RV4-1)") (class "Default")
      (node (ref "R28") (pin "2") (pinfunction "2_2") (pintype "passive"))
      (node (ref "RV4") (pin "R1") (pinfunction "1_R1") (pintype "passive"))
    )
  )
)
